# fan_pwm.net
KiCad netlist of a schematic drawn in EAGLE
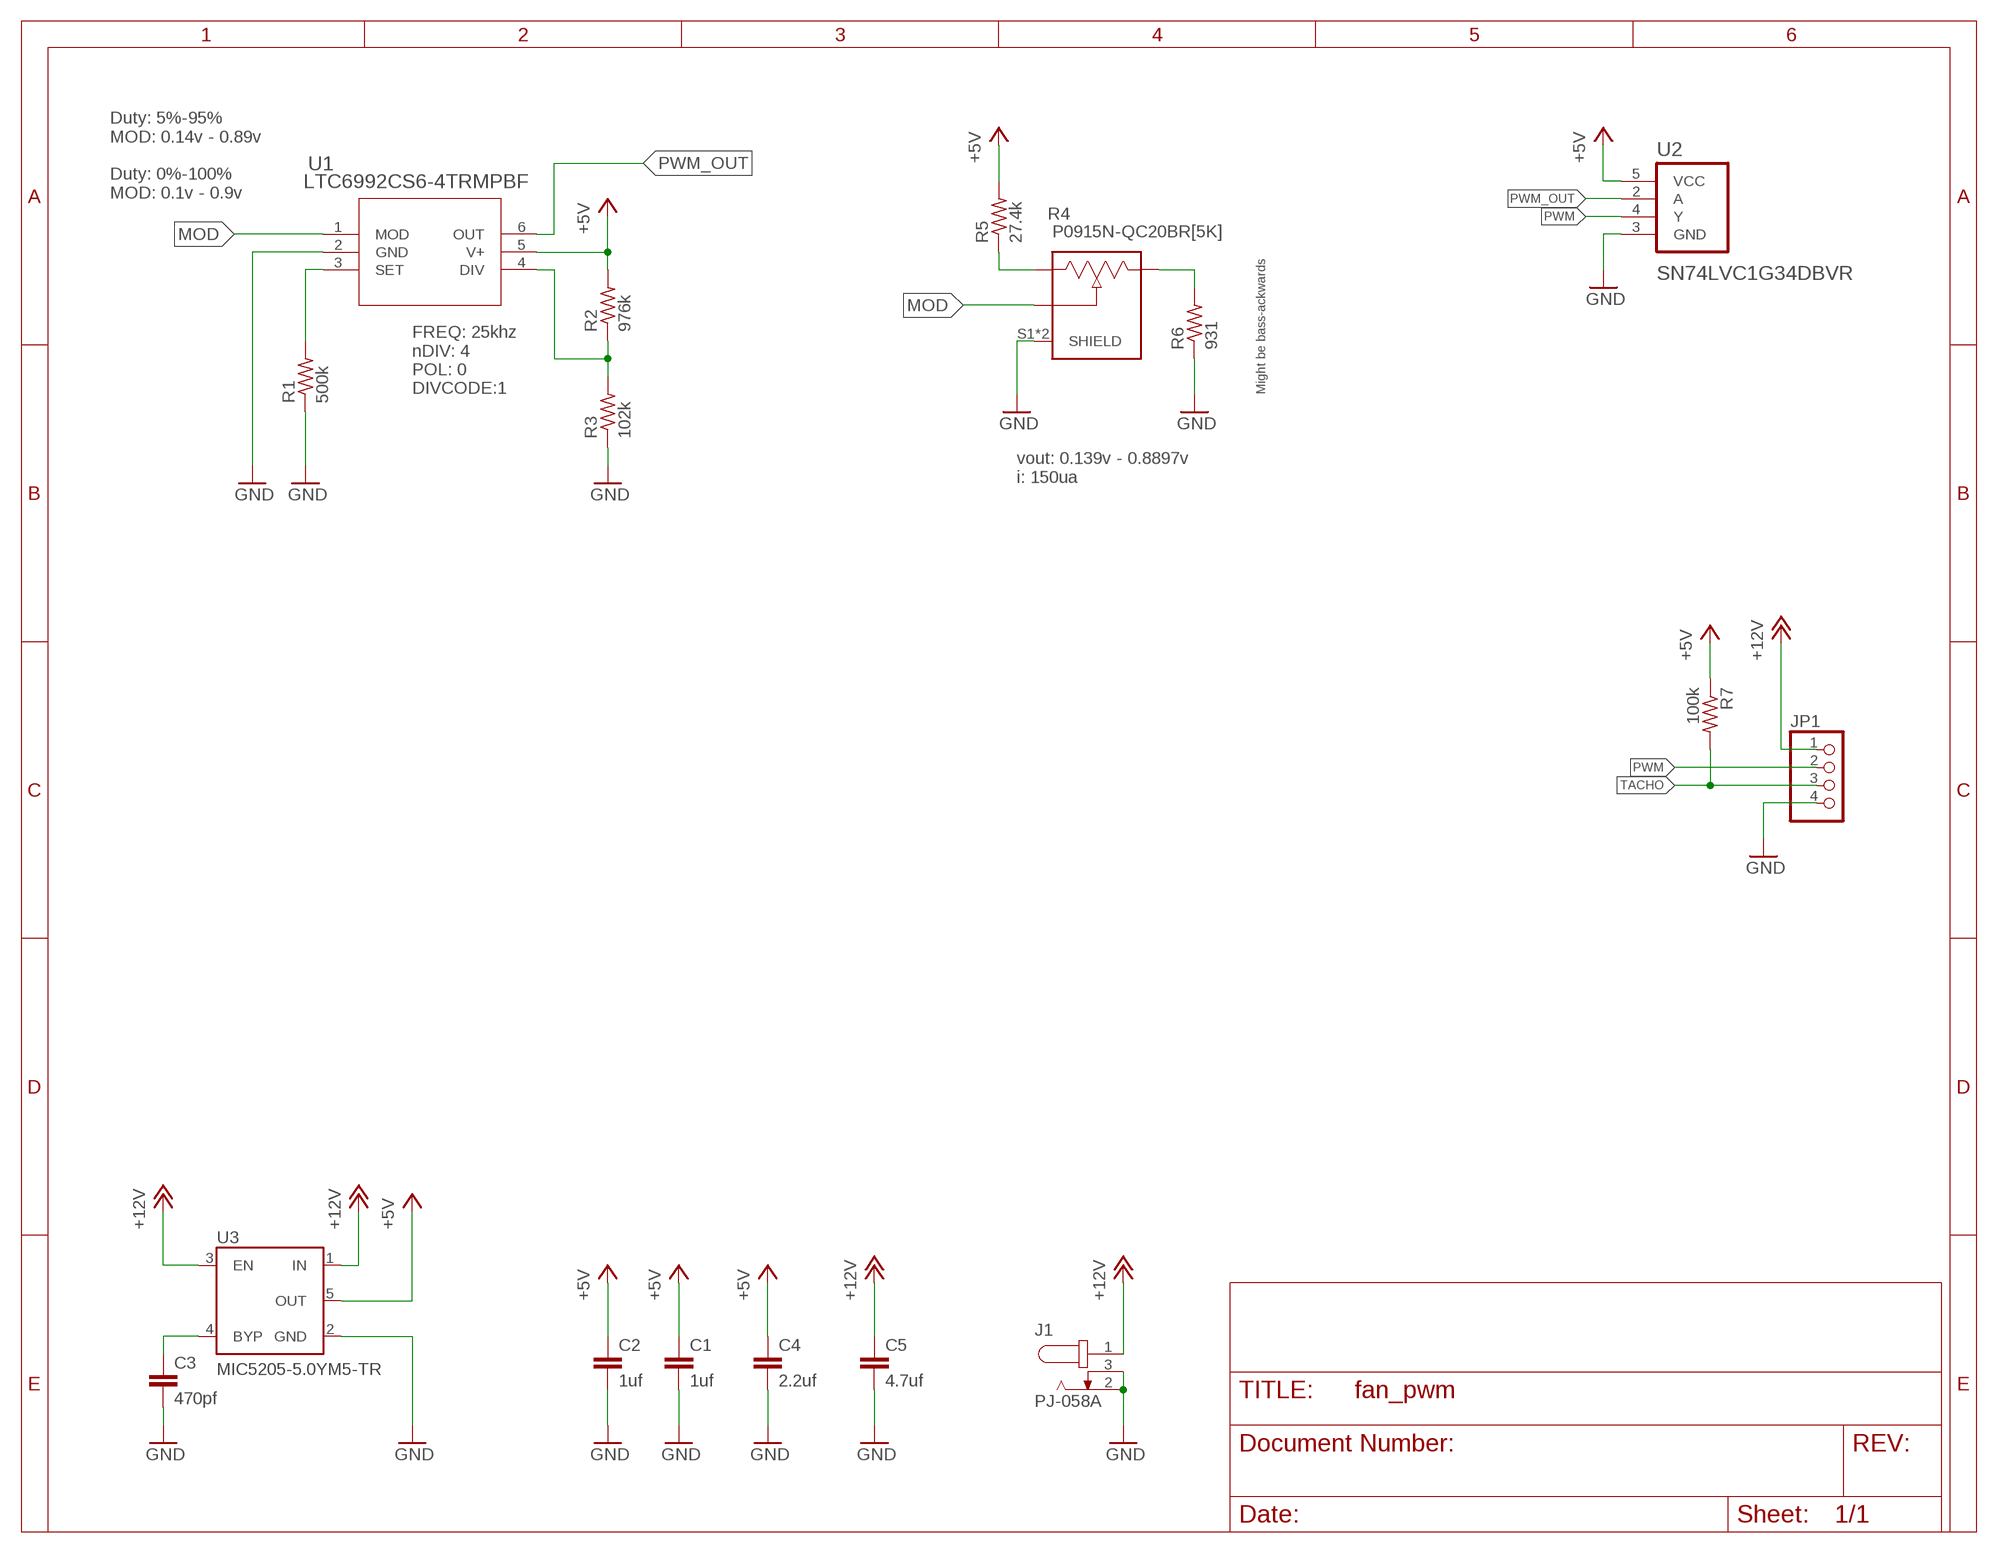
[diagram p0: schematic, sheet 1]

(export (version "E")
  (design (tool "Eeschema 10.0.6"))
  (components
    (comp (ref "C1")
      (value "1uf")
      (footprint "eagle-import:C0805")
      (libsource (lib "eagle-import") (part "C-EUC0805"))
    )
    (comp (ref "C2")
      (value "1uf")
      (footprint "eagle-import:C0805")
      (libsource (lib "eagle-import") (part "C-EUC0805"))
    )
    (comp (ref "C3")
      (value "470pf")
      (footprint "eagle-import:C0805")
      (libsource (lib "eagle-import") (part "C-EUC0805"))
    )
    (comp (ref "C4")
      (value "2.2uf")
      (footprint "eagle-import:C0805")
      (libsource (lib "eagle-import") (part "C-EUC0805"))
    )
    (comp (ref "C5")
      (value "4.7uf")
      (footprint "eagle-import:C0805")
      (libsource (lib "eagle-import") (part "C-EUC0805"))
    )
    (comp (ref "J1")
      (value "PJ-058A")
      (footprint "eagle-import:CUI_PJ-058A")
      (fields (field (name "MF") "CUI Devices"))
      (libsource (lib "eagle-import") (part "PJ-058A"))
    )
    (comp (ref "JP1")
      (value "PINHD-1X4")
      (footprint "eagle-import:1X04")
      (libsource (lib "eagle-import") (part "PINHD-1X4"))
    )
    (comp (ref "R1")
      (value "500k")
      (footprint "eagle-import:R0805")
      (libsource (lib "eagle-import") (part "R-US_R0805"))
    )
    (comp (ref "R2")
      (value "976k")
      (footprint "eagle-import:R0805")
      (libsource (lib "eagle-import") (part "R-US_R0805"))
    )
    (comp (ref "R3")
      (value "102k")
      (footprint "eagle-import:R0805")
      (libsource (lib "eagle-import") (part "R-US_R0805"))
    )
    (comp (ref "R4")
      (value "P0915N-QC20BR[5K]")
      (footprint "eagle-import:TRIM_P0915N-QC20BR5K")
      (fields
        (field (name "DIGI-KEY_PART_NUMBER") "987-1278-ND")
        (field (name "MF") "TT Electronics/BI")
        (field (name "MP") "P0915N-QC20BR5K")
      )
      (libsource (lib "eagle-import") (part "P0915N-QC20BR5K"))
    )
    (comp (ref "R5")
      (value "27.4k")
      (footprint "eagle-import:R0805")
      (libsource (lib "eagle-import") (part "R-US_R0805"))
    )
    (comp (ref "R6")
      (value "931")
      (footprint "eagle-import:R0805")
      (libsource (lib "eagle-import") (part "R-US_R0805"))
    )
    (comp (ref "R7")
      (value "100k")
      (footprint "eagle-import:R0805")
      (libsource (lib "eagle-import") (part "R-US_R0805"))
    )
    (comp (ref "U1")
      (value "LTC6992CS6-4TRMPBF")
      (footprint "eagle-import:TSOT-23_S6_LIT-M")
      (fields
        (field (name "MANUFACTURER_PART_NUMBER") "LTC6992CS6-4#TRMPBF")
        (field (name "COPYRIGHT") "Copyright (C) 2021 Ultra Librarian. All rights reserved.")
      )
      (libsource (lib "eagle-import") (part "LTC6992CS6-4TRMPBFTSOT-23_S6_LIT-M"))
    )
    (comp (ref "U2")
      (value "SN74LVC1G34DBVR")
      (footprint "eagle-import:SOT95P280X145-5N")
      (fields (field (name "DIGI-KEY_PART_NUMBER") "296-17893-1-ND") (field (name "MF") "Texas Instruments"))
      (libsource (lib "eagle-import") (part "SN74LVC1G34DBVR"))
    )
    (comp (ref "U3")
      (value "MIC5205-5.0YM5-TR")
      (footprint "eagle-import:SOT95P280X145-5N")
      (fields (field (name "DIGI-KEY_PART_NUMBER") "576-1261-1-ND") (field (name "MF") "Microchip"))
      (libsource (lib "eagle-import") (part "MIC5205-5.0YM5-TR"))
    )
  )
  (nets
    (net (code "1") (name "+5V") (class "Default")
      (node (ref "C1") (pin "1") (pinfunction "1_1") (pintype "passive"))
      (node (ref "C2") (pin "1") (pinfunction "1_1") (pintype "passive"))
      (node (ref "C4") (pin "1") (pinfunction "1_1") (pintype "passive"))
      (node (ref "R2") (pin "2") (pinfunction "2_2") (pintype "passive"))
      (node (ref "R5") (pin "2") (pinfunction "2_2") (pintype "passive"))
      (node (ref "R7") (pin "1") (pinfunction "1_1") (pintype "passive"))
      (node (ref "U1") (pin "5") (pinfunction "V+_5") (pintype "power_in"))
      (node (ref "U2") (pin "5") (pinfunction "VCC_5") (pintype "power_in"))
      (node (ref "U3") (pin "5") (pinfunction "OUT_5") (pintype "output"))
    )
    (net (code "2") (name "+12V") (class "Default")
      (node (ref "C5") (pin "1") (pinfunction "1_1") (pintype "passive"))
      (node (ref "J1") (pin "1") (pinfunction "1_1") (pintype "passive"))
      (node (ref "JP1") (pin "1") (pinfunction "1_1") (pintype "passive"))
      (node (ref "U3") (pin "1") (pinfunction "IN_1") (pintype "power_in"))
      (node (ref "U3") (pin "3") (pinfunction "EN_3") (pintype "input"))
    )
    (net (code "3") (name "GND") (class "Default")
      (node (ref "C1") (pin "2") (pinfunction "2_2") (pintype "passive"))
      (node (ref "C2") (pin "2") (pinfunction "2_2") (pintype "passive"))
      (node (ref "C3") (pin "2") (pinfunction "2_2") (pintype "passive"))
      (node (ref "C4") (pin "2") (pinfunction "2_2") (pintype "passive"))
      (node (ref "C5") (pin "2") (pinfunction "2_2") (pintype "passive"))
      (node (ref "J1") (pin "2") (pinfunction "2_2") (pintype "passive"))
      (node (ref "J1") (pin "3") (pinfunction "3_3") (pintype "passive"))
      (node (ref "JP1") (pin "4") (pinfunction "4_4") (pintype "passive"))
      (node (ref "R1") (pin "1") (pinfunction "1_1") (pintype "passive"))
      (node (ref "R3") (pin "1") (pinfunction "1_1") (pintype "passive"))
      (node (ref "R4") (pin "S1") (pinfunction "SHIELD_S1") (pintype "passive"))
      (node (ref "R4") (pin "S2") (pinfunction "SHIELD_S2") (pintype "passive"))
      (node (ref "R6") (pin "1") (pinfunction "1_1") (pintype "passive"))
      (node (ref "U1") (pin "2") (pinfunction "GND_2") (pintype "power_in"))
      (node (ref "U2") (pin "3") (pinfunction "GND_3") (pintype "power_in"))
      (node (ref "U3") (pin "2") (pinfunction "GND_2") (pintype "power_in"))
    )
    (net (code "4") (name "MOD") (class "Default")
      (node (ref "R4") (pin "2") (pinfunction "2_2") (pintype "passive"))
      (node (ref "U1") (pin "1") (pinfunction "MOD_1") (pintype "input"))
    )
    (net (code "5") (name "Net-(R4-Pad1)") (class "Default")
      (node (ref "R4") (pin "1") (pinfunction "1_1") (pintype "passive"))
      (node (ref "R5") (pin "1") (pinfunction "1_1") (pintype "passive"))
    )
    (net (code "6") (name "Net-(R4-Pad3)") (class "Default")
      (node (ref "R4") (pin "3") (pinfunction "3_3") (pintype "passive"))
      (node (ref "R6") (pin "2") (pinfunction "2_2") (pintype "passive"))
    )
    (net (code "7") (name "Net-(U1-DIV)") (class "Default")
      (node (ref "R2") (pin "1") (pinfunction "1_1") (pintype "passive"))
      (node (ref "R3") (pin "2") (pinfunction "2_2") (pintype "passive"))
      (node (ref "U1") (pin "4") (pinfunction "DIV_4") (pintype "input"))
    )
    (net (code "8") (name "Net-(U1-SET)") (class "Default")
      (node (ref "R1") (pin "2") (pinfunction "2_2") (pintype "passive"))
      (node (ref "U1") (pin "3") (pinfunction "SET_3") (pintype "input"))
    )
    (net (code "9") (name "Net-(U3-BYP)") (class "Default")
      (node (ref "C3") (pin "1") (pinfunction "1_1") (pintype "passive"))
      (node (ref "U3") (pin "4") (pinfunction "BYP_4") (pintype "passive"))
    )
    (net (code "10") (name "PWM") (class "Default")
      (node (ref "JP1") (pin "2") (pinfunction "2_2") (pintype "passive"))
      (node (ref "U2") (pin "4") (pinfunction "Y_4") (pintype "output"))
    )
    (net (code "11") (name "PWM_OUT") (class "Default")
      (node (ref "U1") (pin "6") (pinfunction "OUT_6") (pintype "output"))
      (node (ref "U2") (pin "2") (pinfunction "A_2") (pintype "power_in"))
    )
    (net (code "12") (name "TACHO") (class "Default")
      (node (ref "JP1") (pin "3") (pinfunction "3_3") (pintype "passive"))
      (node (ref "R7") (pin "2") (pinfunction "2_2") (pintype "passive"))
    )
  )
)
